# LGT8F328P_48PIN.net
KiCad netlist of a schematic drawn in Altium Designer
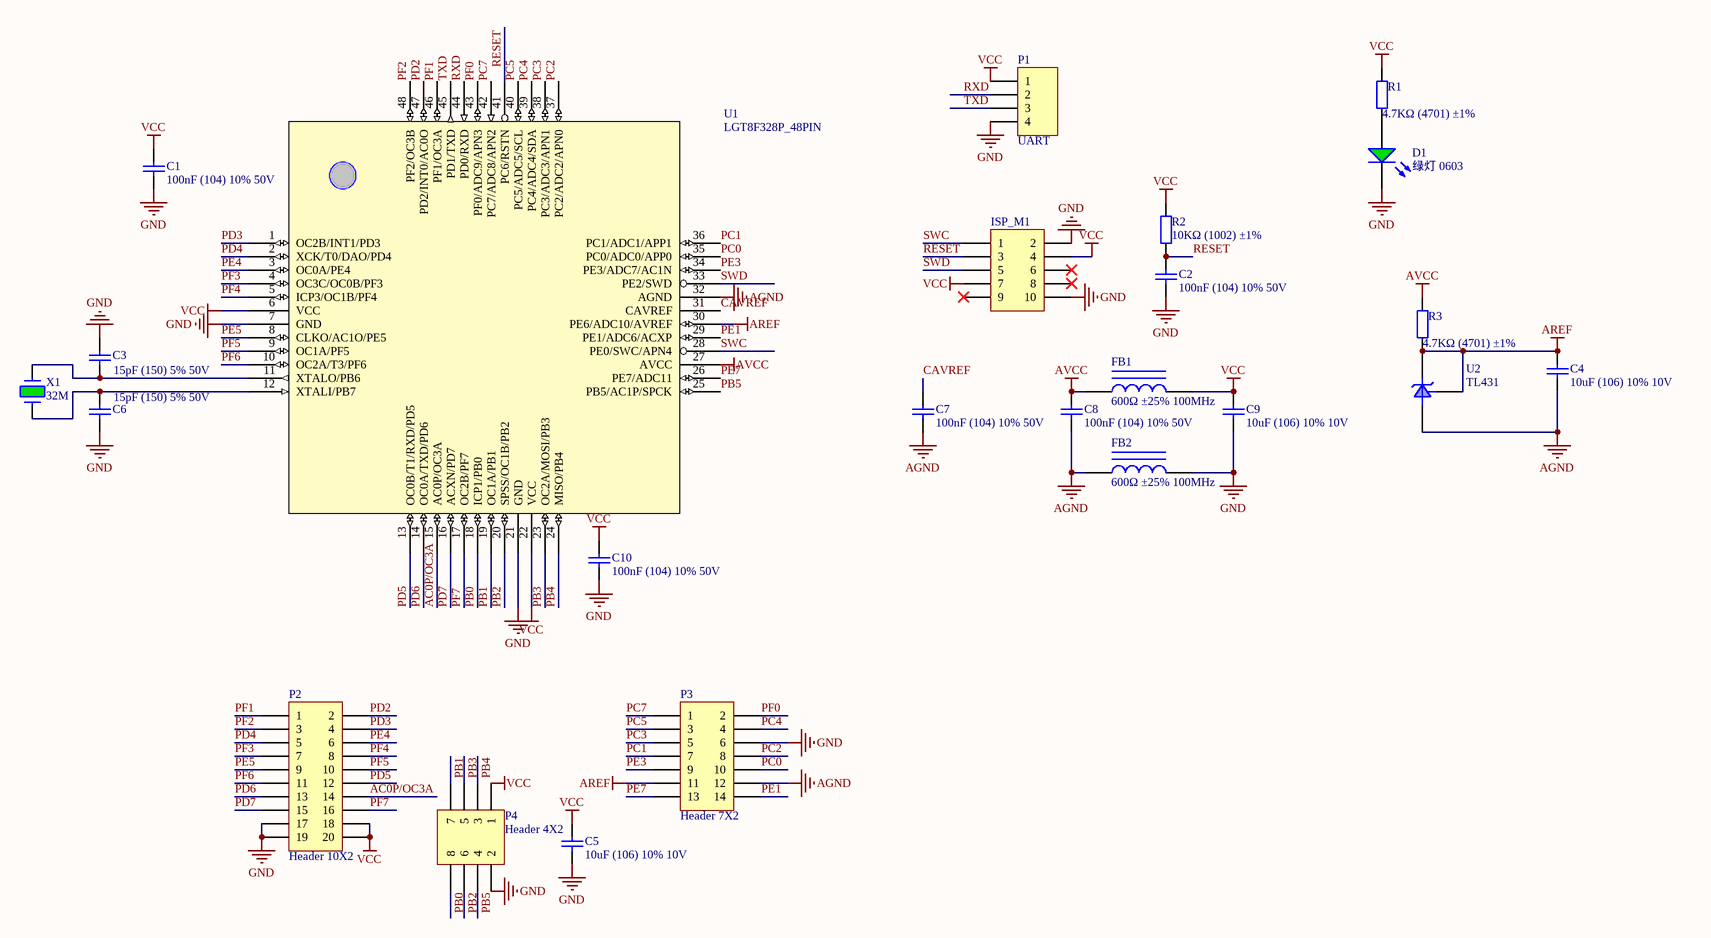
[diagram p0: LGT8F328P_48PIN最小系统.SchDoc]

(export (version "E")
  (design (tool "Eeschema 10.0.6"))
  (components
    (comp (ref "C1")
      (value "100nF (104) 10% 50V")
      (footprint "LC-0603_C")
      (description "贴片电容")
      (libsource (lib "Miscellaneous Devices LC") (part "0603 100nF (104) 10% 50V"))
    )
    (comp (ref "C2")
      (value "100nF (104) 10% 50V")
      (footprint "LC-0603_C")
      (description "贴片电容")
      (libsource (lib "Miscellaneous Devices LC") (part "0603 100nF (104) 10% 50V"))
    )
    (comp (ref "C3")
      (value "15pF (150) 5% 50V")
      (footprint "0603_C")
      (description "贴片电容")
      (libsource (lib "Miscellaneous Devices LC") (part "0603 15pF (150) 5% 50V"))
    )
    (comp (ref "C4")
      (value "10uF (106) 10% 10V")
      (footprint "LC-0603_C")
      (description "贴片电容")
      (libsource (lib "Miscellaneous Devices LC") (part "0603 10uF (106) 10% 10V"))
    )
    (comp (ref "C5")
      (value "10uF (106) 10% 10V")
      (footprint "LC-0603_C")
      (description "贴片电容")
      (libsource (lib "Miscellaneous Devices LC") (part "0603 10uF (106) 10% 10V"))
    )
    (comp (ref "C6")
      (value "15pF (150) 5% 50V")
      (footprint "0603_C")
      (description "贴片电容")
      (libsource (lib "Miscellaneous Devices LC") (part "0603 15pF (150) 5% 50V"))
    )
    (comp (ref "C7")
      (value "100nF (104) 10% 50V")
      (footprint "LC-0603_C")
      (description "贴片电容")
      (libsource (lib "Miscellaneous Devices LC") (part "0603 100nF (104) 10% 50V"))
    )
    (comp (ref "C8")
      (value "100nF (104) 10% 50V")
      (footprint "LC-0603_C")
      (description "贴片电容")
      (libsource (lib "Miscellaneous Devices LC") (part "0603 100nF (104) 10% 50V"))
    )
    (comp (ref "C9")
      (value "10uF (106) 10% 10V")
      (footprint "LC-0603_C")
      (description "贴片电容")
      (libsource (lib "Miscellaneous Devices LC") (part "0603 10uF (106) 10% 10V"))
    )
    (comp (ref "C10")
      (value "100nF (104) 10% 50V")
      (footprint "LC-0603_C")
      (description "贴片电容")
      (libsource (lib "Miscellaneous Devices LC") (part "0603 100nF (104) 10% 50V"))
    )
    (comp (ref "D1")
      (value "绿灯 0603")
      (footprint "0603_LED_S1")
      (description "发光二极管")
      (libsource (lib "Miscellaneous Devices LC") (part "0603 绿灯"))
    )
    (comp (ref "FB1")
      (value "600Ω ±25% 100MHz")
      (footprint "0805_L")
      (description "贴片磁珠")
      (libsource (lib "Miscellaneous Devices LC") (part "0805 600Ω 25% 100MHz"))
    )
    (comp (ref "FB2")
      (value "600Ω ±25% 100MHz")
      (footprint "0805_L")
      (description "贴片磁珠")
      (libsource (lib "Miscellaneous Devices LC") (part "0805 600Ω 25% 100MHz"))
    )
    (comp (ref "ISP_M1")
      (value "ISP2*5")
      (footprint "IDC2x5")
      (description "Header, 5-Pin, Dual row")
      (fields (field (name "PUBLISHER") "Altium Limited"))
      (libsource (lib "myschlib") (part "ISP2*5"))
    )
    (comp (ref "P1")
      (value "UART")
      (footprint "HDR1X4")
      (description "Header, 4-Pin")
      (fields (field (name "PUBLISHER") "Altium Limited"))
      (libsource (lib "Miscellaneous Connectors") (part "Header 4"))
    )
    (comp (ref "P2")
      (value "Header 10X2")
      (footprint "HDR2X10")
      (description "Header, 10-Pin, Dual row")
      (fields (field (name "PUBLISHER") "Altium Limited"))
      (libsource (lib "Miscellaneous Connectors") (part "Header 10X2"))
    )
    (comp (ref "P3")
      (value "Header 7X2")
      (footprint "HDR2X7")
      (description "Header, 7-Pin, Dual row")
      (fields (field (name "PUBLISHER") "Altium Limited"))
      (libsource (lib "Miscellaneous Connectors") (part "Header 7X2"))
    )
    (comp (ref "P4")
      (value "Header 4X2")
      (footprint "HDR2X4")
      (description "Header, 4-Pin, Dual row")
      (fields (field (name "PUBLISHER") "Altium Limited"))
      (libsource (lib "Miscellaneous Connectors") (part "Header 4X2"))
    )
    (comp (ref "R1")
      (value "4.7KΩ (4701) ±1%")
      (footprint "LC-0603_R")
      (description "贴片电阻")
      (libsource (lib "Miscellaneous Devices LC") (part "0603 4.7KΩ (4701) 1%"))
    )
    (comp (ref "R2")
      (value "10KΩ (1002) ±1%")
      (footprint "LC-0603_R")
      (description "贴片电阻")
      (libsource (lib "Miscellaneous Devices LC") (part "0603 10KΩ (1002) 1%"))
    )
    (comp (ref "R3")
      (value "4.7KΩ (4701) ±1%")
      (footprint "LC-0603_R")
      (description "贴片电阻")
      (libsource (lib "Miscellaneous Devices LC") (part "0603 4.7KΩ (4701) 1%"))
    )
    (comp (ref "U1")
      (value "LGT8F328P_48PIN")
      (footprint "LC-LQFP-48_7x7x05P")
      (libsource (lib "LGT8F328P_48PIN") (part "LGT8F328P_48PIN"))
    )
    (comp (ref "U2")
      (value "TL431")
      (footprint "LC-SOT-23(SOT-23-3)")
      (description "电压基准")
      (libsource (lib "Miscellaneous Devices LC") (part "CJ431 0.5%431"))
    )
    (comp (ref "X1")
      (value "32M")
      (footprint "49/S_N")
      (description "Crystal")
      (libsource (lib "Schlib1") (part "CRYSTAL"))
    )
  )
  (nets
    (net (code "1") (name "/AC0P{slash}OC3A") (class "Default")
      (node (ref "P2") (pin "14") (pinfunction "14_14") (pintype "passive"))
      (node (ref "U1") (pin "15") (pinfunction "AC0P/OC3A_15") (pintype "bidirectional"))
    )
    (net (code "2") (name "/CAVREF") (class "Default")
      (node (ref "C7") (pin "2") (pinfunction "2_2") (pintype "passive"))
      (node (ref "U1") (pin "31") (pinfunction "CAVREF_31") (pintype "passive"))
    )
    (net (code "3") (name "/PB0") (class "Default")
      (node (ref "P4") (pin "8") (pinfunction "8_8") (pintype "passive"))
      (node (ref "U1") (pin "18") (pinfunction "ICP1/PB0_18") (pintype "bidirectional"))
    )
    (net (code "4") (name "/PB1") (class "Default")
      (node (ref "P4") (pin "7") (pinfunction "7_7") (pintype "passive"))
      (node (ref "U1") (pin "19") (pinfunction "OC1A/PB1_19") (pintype "bidirectional"))
    )
    (net (code "5") (name "/PB2") (class "Default")
      (node (ref "P4") (pin "6") (pinfunction "6_6") (pintype "passive"))
      (node (ref "U1") (pin "20") (pinfunction "SPSS/OC1B/PB2_20") (pintype "bidirectional"))
    )
    (net (code "6") (name "/PB3") (class "Default")
      (node (ref "P4") (pin "5") (pinfunction "5_5") (pintype "passive"))
      (node (ref "U1") (pin "23") (pinfunction "OC2A/MOSI/PB3_23") (pintype "bidirectional"))
    )
    (net (code "7") (name "/PB4") (class "Default")
      (node (ref "P4") (pin "3") (pinfunction "3_3") (pintype "passive"))
      (node (ref "U1") (pin "24") (pinfunction "MISO/PB4_24") (pintype "bidirectional"))
    )
    (net (code "8") (name "/PB5") (class "Default")
      (node (ref "P4") (pin "4") (pinfunction "4_4") (pintype "passive"))
      (node (ref "U1") (pin "25") (pinfunction "PB5/AC1P/SPCK_25") (pintype "bidirectional"))
    )
    (net (code "9") (name "/PC0") (class "Default")
      (node (ref "P3") (pin "10") (pinfunction "10_10") (pintype "passive"))
      (node (ref "U1") (pin "35") (pinfunction "PC0/ADC0/APP0_35") (pintype "bidirectional"))
    )
    (net (code "10") (name "/PC1") (class "Default")
      (node (ref "P3") (pin "7") (pinfunction "7_7") (pintype "passive"))
      (node (ref "U1") (pin "36") (pinfunction "PC1/ADC1/APP1_36") (pintype "bidirectional"))
    )
    (net (code "11") (name "/PC2") (class "Default")
      (node (ref "P3") (pin "8") (pinfunction "8_8") (pintype "passive"))
      (node (ref "U1") (pin "37") (pinfunction "PC2/ADC2/APN0_37") (pintype "bidirectional"))
    )
    (net (code "12") (name "/PC3") (class "Default")
      (node (ref "P3") (pin "5") (pinfunction "5_5") (pintype "passive"))
      (node (ref "U1") (pin "38") (pinfunction "PC3/ADC3/APN1_38") (pintype "bidirectional"))
    )
    (net (code "13") (name "/PC4") (class "Default")
      (node (ref "P3") (pin "4") (pinfunction "4_4") (pintype "passive"))
      (node (ref "U1") (pin "39") (pinfunction "PC4/ADC4/SDA_39") (pintype "bidirectional"))
    )
    (net (code "14") (name "/PC5") (class "Default")
      (node (ref "P3") (pin "3") (pinfunction "3_3") (pintype "passive"))
      (node (ref "U1") (pin "40") (pinfunction "PC5/ADC5/SCL_40") (pintype "bidirectional"))
    )
    (net (code "15") (name "/PC7") (class "Default")
      (node (ref "P3") (pin "1") (pinfunction "1_1") (pintype "passive"))
      (node (ref "U1") (pin "42") (pinfunction "PC7/ADC8/APN2_42") (pintype "input"))
    )
    (net (code "16") (name "/PD2") (class "Default")
      (node (ref "P2") (pin "2") (pinfunction "2_2") (pintype "passive"))
      (node (ref "U1") (pin "47") (pinfunction "PD2/INT0/AC0O_47") (pintype "bidirectional"))
    )
    (net (code "17") (name "/PD3") (class "Default")
      (node (ref "P2") (pin "4") (pinfunction "4_4") (pintype "passive"))
      (node (ref "U1") (pin "1") (pinfunction "OC2B/INT1/PD3_1") (pintype "bidirectional"))
    )
    (net (code "18") (name "/PD4") (class "Default")
      (node (ref "P2") (pin "5") (pinfunction "5_5") (pintype "passive"))
      (node (ref "U1") (pin "2") (pinfunction "XCK/T0/DAO/PD4_2") (pintype "bidirectional"))
    )
    (net (code "19") (name "/PD5") (class "Default")
      (node (ref "P2") (pin "12") (pinfunction "12_12") (pintype "passive"))
      (node (ref "U1") (pin "13") (pinfunction "OC0B/T1/RXD/PD5_13") (pintype "bidirectional"))
    )
    (net (code "20") (name "/PD6") (class "Default")
      (node (ref "P2") (pin "13") (pinfunction "13_13") (pintype "passive"))
      (node (ref "U1") (pin "14") (pinfunction "OC0A/TXD/PD6_14") (pintype "bidirectional"))
    )
    (net (code "21") (name "/PD7") (class "Default")
      (node (ref "P2") (pin "15") (pinfunction "15_15") (pintype "passive"))
      (node (ref "U1") (pin "16") (pinfunction "ACXN/PD7_16") (pintype "bidirectional"))
    )
    (net (code "22") (name "/PE1") (class "Default")
      (node (ref "P3") (pin "14") (pinfunction "14_14") (pintype "passive"))
      (node (ref "U1") (pin "29") (pinfunction "PE1/ADC6/ACXP_29") (pintype "bidirectional"))
    )
    (net (code "23") (name "/PE3") (class "Default")
      (node (ref "P3") (pin "9") (pinfunction "9_9") (pintype "passive"))
      (node (ref "U1") (pin "34") (pinfunction "PE3/ADC7/AC1N_34") (pintype "bidirectional"))
    )
    (net (code "24") (name "/PE4") (class "Default")
      (node (ref "P2") (pin "6") (pinfunction "6_6") (pintype "passive"))
      (node (ref "U1") (pin "3") (pinfunction "OC0A/PE4_3") (pintype "bidirectional"))
    )
    (net (code "25") (name "/PE5") (class "Default")
      (node (ref "P2") (pin "9") (pinfunction "9_9") (pintype "passive"))
      (node (ref "U1") (pin "8") (pinfunction "CLKO/AC1O/PE5_8") (pintype "bidirectional"))
    )
    (net (code "26") (name "/PE7") (class "Default")
      (node (ref "P3") (pin "13") (pinfunction "13_13") (pintype "passive"))
      (node (ref "U1") (pin "26") (pinfunction "PE7/ADC11_26") (pintype "bidirectional"))
    )
    (net (code "27") (name "/PF0") (class "Default")
      (node (ref "P3") (pin "2") (pinfunction "2_2") (pintype "passive"))
      (node (ref "U1") (pin "43") (pinfunction "PF0/ADC9/APN3_43") (pintype "bidirectional"))
    )
    (net (code "28") (name "/PF1") (class "Default")
      (node (ref "P2") (pin "1") (pinfunction "1_1") (pintype "passive"))
      (node (ref "U1") (pin "46") (pinfunction "PF1/OC3A_46") (pintype "bidirectional"))
    )
    (net (code "29") (name "/PF2") (class "Default")
      (node (ref "P2") (pin "3") (pinfunction "3_3") (pintype "passive"))
      (node (ref "U1") (pin "48") (pinfunction "PF2/OC3B_48") (pintype "bidirectional"))
    )
    (net (code "30") (name "/PF3") (class "Default")
      (node (ref "P2") (pin "7") (pinfunction "7_7") (pintype "passive"))
      (node (ref "U1") (pin "4") (pinfunction "OC3C/OC0B/PF3_4") (pintype "bidirectional"))
    )
    (net (code "31") (name "/PF4") (class "Default")
      (node (ref "P2") (pin "8") (pinfunction "8_8") (pintype "passive"))
      (node (ref "U1") (pin "5") (pinfunction "ICP3/OC1B/PF4_5") (pintype "bidirectional"))
    )
    (net (code "32") (name "/PF5") (class "Default")
      (node (ref "P2") (pin "10") (pinfunction "10_10") (pintype "passive"))
      (node (ref "U1") (pin "9") (pinfunction "OC1A/PF5_9") (pintype "bidirectional"))
    )
    (net (code "33") (name "/PF6") (class "Default")
      (node (ref "P2") (pin "11") (pinfunction "11_11") (pintype "passive"))
      (node (ref "U1") (pin "10") (pinfunction "OC2A/T3/PF6_10") (pintype "bidirectional"))
    )
    (net (code "34") (name "/PF7") (class "Default")
      (node (ref "P2") (pin "16") (pinfunction "16_16") (pintype "passive"))
      (node (ref "U1") (pin "17") (pinfunction "OC2B/PF7_17") (pintype "bidirectional"))
    )
    (net (code "35") (name "/RESET") (class "Default")
      (node (ref "C2") (pin "2") (pinfunction "2_2") (pintype "passive"))
      (node (ref "ISP_M1") (pin "3") (pinfunction "3_3") (pintype "passive"))
      (node (ref "R2") (pin "1") (pinfunction "1_1") (pintype "passive"))
      (node (ref "U1") (pin "41") (pinfunction "PC6/RSTN_41") (pintype "passive"))
    )
    (net (code "36") (name "/RXD") (class "Default")
      (node (ref "P1") (pin "2") (pinfunction "2_2") (pintype "passive"))
      (node (ref "U1") (pin "44") (pinfunction "PD0/RXD_44") (pintype "input"))
    )
    (net (code "37") (name "/SWC") (class "Default")
      (node (ref "ISP_M1") (pin "1") (pinfunction "1_1") (pintype "passive"))
      (node (ref "U1") (pin "28") (pinfunction "PE0/SWC/APN4_28") (pintype "passive"))
    )
    (net (code "38") (name "/SWD") (class "Default")
      (node (ref "ISP_M1") (pin "5") (pinfunction "5_5") (pintype "passive"))
      (node (ref "U1") (pin "33") (pinfunction "PE2/SWD_33") (pintype "passive"))
    )
    (net (code "39") (name "/TXD") (class "Default")
      (node (ref "P1") (pin "3") (pinfunction "3_3") (pintype "passive"))
      (node (ref "U1") (pin "45") (pinfunction "PD1/TXD_45") (pintype "output"))
    )
    (net (code "40") (name "AGND") (class "Default")
      (node (ref "C4") (pin "1") (pinfunction "1_1") (pintype "passive"))
      (node (ref "C7") (pin "1") (pinfunction "1_1") (pintype "passive"))
      (node (ref "C8") (pin "1") (pinfunction "1_1") (pintype "passive"))
      (node (ref "FB2") (pin "1") (pinfunction "1_1") (pintype "passive"))
      (node (ref "P3") (pin "12") (pinfunction "12_12") (pintype "passive"))
      (node (ref "U1") (pin "32") (pinfunction "AGND_32") (pintype "power_in"))
      (node (ref "U2") (pin "3") (pinfunction "A_3") (pintype "passive"))
    )
    (net (code "41") (name "AREF") (class "Default")
      (node (ref "C4") (pin "2") (pinfunction "2_2") (pintype "passive"))
      (node (ref "P3") (pin "11") (pinfunction "11_11") (pintype "passive"))
      (node (ref "R3") (pin "1") (pinfunction "1_1") (pintype "passive"))
      (node (ref "U1") (pin "30") (pinfunction "PE6/ADC10/AVREF_30") (pintype "bidirectional"))
      (node (ref "U2") (pin "1") (pinfunction "R_1") (pintype "passive"))
      (node (ref "U2") (pin "2") (pinfunction "K_2") (pintype "passive"))
    )
    (net (code "42") (name "AVCC") (class "Default")
      (node (ref "C8") (pin "2") (pinfunction "2_2") (pintype "passive"))
      (node (ref "FB1") (pin "1") (pinfunction "1_1") (pintype "passive"))
      (node (ref "R3") (pin "2") (pinfunction "2_2") (pintype "passive"))
      (node (ref "U1") (pin "27") (pinfunction "AVCC_27") (pintype "power_in"))
    )
    (net (code "43") (name "GND") (class "Default")
      (node (ref "C1") (pin "2") (pinfunction "2_2") (pintype "passive"))
      (node (ref "C10") (pin "2") (pinfunction "2_2") (pintype "passive"))
      (node (ref "C2") (pin "1") (pinfunction "1_1") (pintype "passive"))
      (node (ref "C3") (pin "2") (pinfunction "2_2") (pintype "passive"))
      (node (ref "C5") (pin "1") (pinfunction "1_1") (pintype "passive"))
      (node (ref "C6") (pin "1") (pinfunction "1_1") (pintype "passive"))
      (node (ref "C9") (pin "1") (pinfunction "1_1") (pintype "passive"))
      (node (ref "D1") (pin "K") (pinfunction "K_K") (pintype "passive"))
      (node (ref "FB2") (pin "2") (pinfunction "2_2") (pintype "passive"))
      (node (ref "ISP_M1") (pin "10") (pinfunction "10_10") (pintype "passive"))
      (node (ref "ISP_M1") (pin "2") (pinfunction "2_2") (pintype "passive"))
      (node (ref "P1") (pin "4") (pinfunction "4_4") (pintype "passive"))
      (node (ref "P2") (pin "17") (pinfunction "17_17") (pintype "passive"))
      (node (ref "P2") (pin "19") (pinfunction "19_19") (pintype "passive"))
      (node (ref "P3") (pin "6") (pinfunction "6_6") (pintype "passive"))
      (node (ref "P4") (pin "2") (pinfunction "2_2") (pintype "passive"))
      (node (ref "U1") (pin "21") (pinfunction "GND_21") (pintype "power_in"))
      (node (ref "U1") (pin "7") (pinfunction "GND_7") (pintype "power_in"))
    )
    (net (code "44") (name "Net-(D1-PadA)") (class "Default")
      (node (ref "D1") (pin "A") (pinfunction "A_A") (pintype "passive"))
      (node (ref "R1") (pin "1") (pinfunction "1_1") (pintype "passive"))
    )
    (net (code "45") (name "Net-(U1-XTALI{slash}PB7)") (class "Default")
      (node (ref "C6") (pin "2") (pinfunction "2_2") (pintype "passive"))
      (node (ref "U1") (pin "12") (pinfunction "XTALI/PB7_12") (pintype "input"))
      (node (ref "X1") (pin "2") (pinfunction "2_2") (pintype "passive"))
    )
    (net (code "46") (name "Net-(U1-XTALO{slash}PB6)") (class "Default")
      (node (ref "C3") (pin "1") (pinfunction "1_1") (pintype "passive"))
      (node (ref "U1") (pin "11") (pinfunction "XTALO/PB6_11") (pintype "output"))
      (node (ref "X1") (pin "1") (pinfunction "1_1") (pintype "passive"))
    )
    (net (code "47") (name "VCC") (class "Default")
      (node (ref "C1") (pin "1") (pinfunction "1_1") (pintype "passive"))
      (node (ref "C10") (pin "1") (pinfunction "1_1") (pintype "passive"))
      (node (ref "C5") (pin "2") (pinfunction "2_2") (pintype "passive"))
      (node (ref "C9") (pin "2") (pinfunction "2_2") (pintype "passive"))
      (node (ref "FB1") (pin "2") (pinfunction "2_2") (pintype "passive"))
      (node (ref "ISP_M1") (pin "4") (pinfunction "4_4") (pintype "passive"))
      (node (ref "ISP_M1") (pin "7") (pinfunction "7_7") (pintype "passive"))
      (node (ref "P1") (pin "1") (pinfunction "1_1") (pintype "passive"))
      (node (ref "P2") (pin "18") (pinfunction "18_18") (pintype "passive"))
      (node (ref "P2") (pin "20") (pinfunction "20_20") (pintype "passive"))
      (node (ref "P4") (pin "1") (pinfunction "1_1") (pintype "passive"))
      (node (ref "R1") (pin "2") (pinfunction "2_2") (pintype "passive"))
      (node (ref "R2") (pin "2") (pinfunction "2_2") (pintype "passive"))
      (node (ref "U1") (pin "22") (pinfunction "VCC_22") (pintype "power_in"))
      (node (ref "U1") (pin "6") (pinfunction "VCC_6") (pintype "power_in"))
    )
    (net (code "48") (name "unconnected-(ISP_M1-Pad6)") (class "Default")
      (node (ref "ISP_M1") (pin "6") (pinfunction "6_6") (pintype "passive+no_connect"))
    )
    (net (code "49") (name "unconnected-(ISP_M1-Pad8)") (class "Default")
      (node (ref "ISP_M1") (pin "8") (pinfunction "8_8") (pintype "passive+no_connect"))
    )
    (net (code "50") (name "unconnected-(ISP_M1-Pad9)") (class "Default")
      (node (ref "ISP_M1") (pin "9") (pinfunction "9_9") (pintype "passive+no_connect"))
    )
  )
)
